# powerTestv2-0.net
KiCad netlist of a schematic drawn in EAGLE
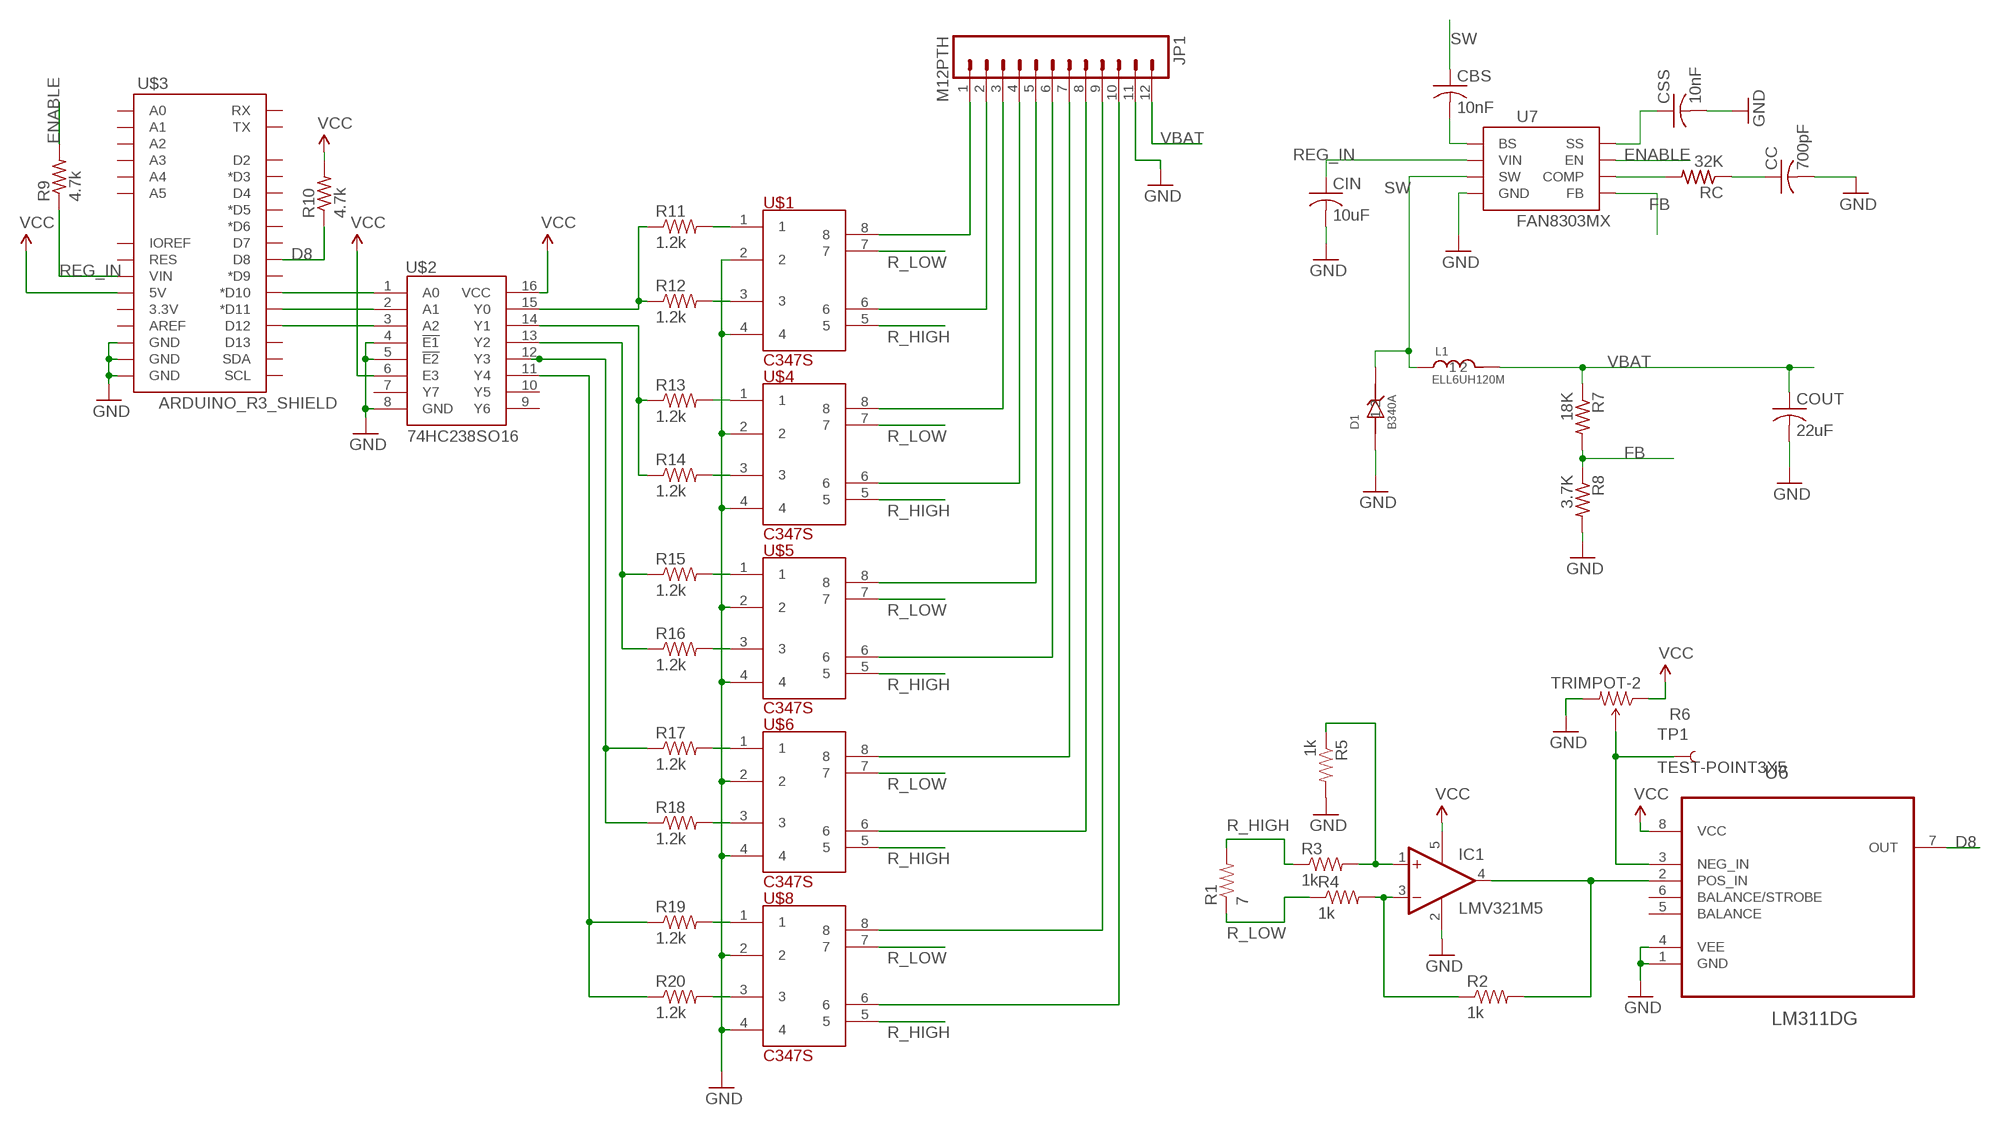
[diagram p0: schematic, sheet 1]

(export (version "E")
  (design (tool "Eeschema 10.0.6"))
  (components
    (comp (ref "CBS")
      (value "10nF")
      (footprint "eagle-import:C0603")
      (libsource (lib "eagle-import") (part "C-USC0603"))
    )
    (comp (ref "CC")
      (value "700pF")
      (footprint "eagle-import:C0603")
      (libsource (lib "eagle-import") (part "C-USC0603"))
    )
    (comp (ref "CIN")
      (value "10uF")
      (footprint "eagle-import:C0603")
      (libsource (lib "eagle-import") (part "C-USC0603"))
    )
    (comp (ref "COUT")
      (value "22uF")
      (footprint "eagle-import:C0603")
      (libsource (lib "eagle-import") (part "C-USC0603"))
    )
    (comp (ref "CSS")
      (value "10nF")
      (footprint "eagle-import:C0603")
      (libsource (lib "eagle-import") (part "C-USC0603"))
    )
    (comp (ref "D1")
      (value "B340A")
      (footprint "eagle-import:B340A")
      (libsource (lib "eagle-import") (part "B340A"))
    )
    (comp (ref "IC1")
      (value "LMV321M5")
      (footprint "eagle-import:SOT23-5")
      (libsource (lib "eagle-import") (part "LMV321?M5"))
    )
    (comp (ref "JP1")
      (value "M12PTH")
      (footprint "eagle-import:1X12")
      (libsource (lib "eagle-import") (part "M12PTH"))
    )
    (comp (ref "L1")
      (value "ELL6UH120M")
      (footprint "eagle-import:ELL6UH120M")
      (libsource (lib "eagle-import") (part "ELL6UH120M"))
    )
    (comp (ref "R1")
      (value "7")
      (footprint "eagle-import:AXIAL-0.8")
      (libsource (lib "eagle-import") (part "SparkFun-Resistors_RESISTORPTH-2W"))
    )
    (comp (ref "R2")
      (value "1k")
      (footprint "eagle-import:0603-RES")
      (libsource (lib "eagle-import") (part "RESISTOR0603-RES"))
    )
    (comp (ref "R3")
      (value "1k")
      (footprint "eagle-import:0603-RES")
      (libsource (lib "eagle-import") (part "RESISTOR0603-RES"))
    )
    (comp (ref "R4")
      (value "1k")
      (footprint "eagle-import:0603-RES")
      (libsource (lib "eagle-import") (part "RESISTOR0603-RES"))
    )
    (comp (ref "R5")
      (value "1k")
      (footprint "eagle-import:0603-RES")
      (libsource (lib "eagle-import") (part "RESISTOR0603-RES"))
    )
    (comp (ref "R6")
      (value "TRIMPOT-2")
      (footprint "eagle-import:TRIMPOT_TC33")
      (libsource (lib "eagle-import") (part "TRIMPOT-2"))
    )
    (comp (ref "R7")
      (value "18K")
      (footprint "eagle-import:R0603")
      (libsource (lib "eagle-import") (part "R-US_R0603"))
    )
    (comp (ref "R8")
      (value "3.7K")
      (footprint "eagle-import:R0603")
      (libsource (lib "eagle-import") (part "R-US_R0603"))
    )
    (comp (ref "R9")
      (value "4.7k")
      (footprint "eagle-import:R0603")
      (libsource (lib "eagle-import") (part "R-US_R0603"))
    )
    (comp (ref "R10")
      (value "4.7k")
      (footprint "eagle-import:R0603")
      (libsource (lib "eagle-import") (part "R-US_R0603"))
    )
    (comp (ref "R11")
      (value "1.2k")
      (footprint "eagle-import:0603-RES")
      (libsource (lib "eagle-import") (part "RESISTOR0603-RES"))
    )
    (comp (ref "R12")
      (value "1.2k")
      (footprint "eagle-import:0603-RES")
      (libsource (lib "eagle-import") (part "RESISTOR0603-RES"))
    )
    (comp (ref "R13")
      (value "1.2k")
      (footprint "eagle-import:0603-RES")
      (libsource (lib "eagle-import") (part "RESISTOR0603-RES"))
    )
    (comp (ref "R14")
      (value "1.2k")
      (footprint "eagle-import:0603-RES")
      (libsource (lib "eagle-import") (part "RESISTOR0603-RES"))
    )
    (comp (ref "R15")
      (value "1.2k")
      (footprint "eagle-import:0603-RES")
      (libsource (lib "eagle-import") (part "RESISTOR0603-RES"))
    )
    (comp (ref "R16")
      (value "1.2k")
      (footprint "eagle-import:0603-RES")
      (libsource (lib "eagle-import") (part "RESISTOR0603-RES"))
    )
    (comp (ref "R17")
      (value "1.2k")
      (footprint "eagle-import:0603-RES")
      (libsource (lib "eagle-import") (part "RESISTOR0603-RES"))
    )
    (comp (ref "R18")
      (value "1.2k")
      (footprint "eagle-import:0603-RES")
      (libsource (lib "eagle-import") (part "RESISTOR0603-RES"))
    )
    (comp (ref "R19")
      (value "1.2k")
      (footprint "eagle-import:0603-RES")
      (libsource (lib "eagle-import") (part "RESISTOR0603-RES"))
    )
    (comp (ref "R20")
      (value "1.2k")
      (footprint "eagle-import:0603-RES")
      (libsource (lib "eagle-import") (part "RESISTOR0603-RES"))
    )
    (comp (ref "RC")
      (value "32K")
      (footprint "eagle-import:R0603")
      (libsource (lib "eagle-import") (part "R-US_R0603"))
    )
    (comp (ref "TP1")
      (value "TEST-POINT3X5")
      (footprint "eagle-import:PAD.03X.05")
      (libsource (lib "eagle-import") (part "TEST-POINT3X5"))
    )
    (comp (ref "U$1")
      (value "C347S")
      (footprint "eagle-import:SOP8")
      (libsource (lib "eagle-import") (part "C347S"))
    )
    (comp (ref "U$2")
      (value "74HC238SO16")
      (footprint "eagle-import:SO16")
      (libsource (lib "eagle-import") (part "74HC238SO16"))
    )
    (comp (ref "U$3")
      (value "ARDUINO_R3_SHIELD")
      (footprint "eagle-import:UNO_R3_SHIELD")
      (libsource (lib "eagle-import") (part "ARDUINO_R3_SHIELD"))
    )
    (comp (ref "U$4")
      (value "C347S")
      (footprint "eagle-import:SOP8")
      (libsource (lib "eagle-import") (part "C347S"))
    )
    (comp (ref "U$5")
      (value "C347S")
      (footprint "eagle-import:SOP8")
      (libsource (lib "eagle-import") (part "C347S"))
    )
    (comp (ref "U$6")
      (value "C347S")
      (footprint "eagle-import:SOP8")
      (libsource (lib "eagle-import") (part "C347S"))
    )
    (comp (ref "U$8")
      (value "C347S")
      (footprint "eagle-import:SOP8")
      (libsource (lib "eagle-import") (part "C347S"))
    )
    (comp (ref "U6")
      (value "LM311DG")
      (footprint "eagle-import:SOIC127P600X175-8N")
      (libsource (lib "eagle-import") (part "LM311DG"))
    )
    (comp (ref "U7")
      (value "FAN8303MX")
      (footprint "eagle-import:FAN8303MX")
      (libsource (lib "eagle-import") (part "FAN8303MX"))
    )
  )
  (nets
    (net (code "1") (name "/D8") (class "Default")
      (node (ref "R10") (pin "1") (pinfunction "1_1") (pintype "passive"))
      (node (ref "U$3") (pin "D8") (pinfunction "D8_D8") (pintype "bidirectional"))
      (node (ref "U6") (pin "7") (pinfunction "OUT_7") (pintype "output"))
    )
    (net (code "2") (name "/ENABLE") (class "Default")
      (node (ref "R9") (pin "2") (pinfunction "2_2") (pintype "passive"))
      (node (ref "U7") (pin "P$7") (pinfunction "EN_P$7") (pintype "bidirectional"))
    )
    (net (code "3") (name "/FB") (class "Default")
      (node (ref "R7") (pin "2") (pinfunction "2_2") (pintype "passive"))
      (node (ref "R8") (pin "1") (pinfunction "1_1") (pintype "passive"))
      (node (ref "U7") (pin "P$5") (pinfunction "FB_P$5") (pintype "bidirectional"))
    )
    (net (code "4") (name "/REG_IN") (class "Default")
      (node (ref "CIN") (pin "1") (pinfunction "1_1") (pintype "passive"))
      (node (ref "R9") (pin "1") (pinfunction "1_1") (pintype "passive"))
      (node (ref "U$3") (pin "VIN") (pinfunction "VIN_VIN") (pintype "bidirectional"))
      (node (ref "U7") (pin "P$2") (pinfunction "VIN_P$2") (pintype "bidirectional"))
    )
    (net (code "5") (name "/R_HIGH") (class "Default")
      (node (ref "R1") (pin "P$2") (pinfunction "2_P$2") (pintype "passive"))
      (node (ref "R3") (pin "1") (pinfunction "1_1") (pintype "passive"))
      (node (ref "U$1") (pin "5") (pinfunction "5_5") (pintype "bidirectional"))
      (node (ref "U$4") (pin "5") (pinfunction "5_5") (pintype "bidirectional"))
      (node (ref "U$5") (pin "5") (pinfunction "5_5") (pintype "bidirectional"))
      (node (ref "U$6") (pin "5") (pinfunction "5_5") (pintype "bidirectional"))
      (node (ref "U$8") (pin "5") (pinfunction "5_5") (pintype "bidirectional"))
    )
    (net (code "6") (name "/R_LOW") (class "Default")
      (node (ref "R1") (pin "P$1") (pinfunction "1_P$1") (pintype "passive"))
      (node (ref "R4") (pin "1") (pinfunction "1_1") (pintype "passive"))
      (node (ref "U$1") (pin "7") (pinfunction "7_7") (pintype "bidirectional"))
      (node (ref "U$4") (pin "7") (pinfunction "7_7") (pintype "bidirectional"))
      (node (ref "U$5") (pin "7") (pinfunction "7_7") (pintype "bidirectional"))
      (node (ref "U$6") (pin "7") (pinfunction "7_7") (pintype "bidirectional"))
      (node (ref "U$8") (pin "7") (pinfunction "7_7") (pintype "bidirectional"))
    )
    (net (code "7") (name "/SW") (class "Default")
      (node (ref "CBS") (pin "1") (pinfunction "1_1") (pintype "passive"))
      (node (ref "D1") (pin "P$2") (pinfunction "2_P$2") (pintype "bidirectional"))
      (node (ref "L1") (pin "P$1") (pinfunction "1_P$1") (pintype "bidirectional"))
      (node (ref "U7") (pin "P$3") (pinfunction "SW_P$3") (pintype "bidirectional"))
    )
    (net (code "8") (name "/VBAT") (class "Default")
      (node (ref "COUT") (pin "1") (pinfunction "1_1") (pintype "passive"))
      (node (ref "JP1") (pin "12") (pinfunction "12_12") (pintype "passive"))
      (node (ref "L1") (pin "P$2") (pinfunction "2_P$2") (pintype "bidirectional"))
      (node (ref "R7") (pin "1") (pinfunction "1_1") (pintype "passive"))
    )
    (net (code "9") (name "GND") (class "Default")
      (node (ref "CC") (pin "2") (pinfunction "2_2") (pintype "passive"))
      (node (ref "CIN") (pin "2") (pinfunction "2_2") (pintype "passive"))
      (node (ref "COUT") (pin "2") (pinfunction "2_2") (pintype "passive"))
      (node (ref "CSS") (pin "2") (pinfunction "2_2") (pintype "passive"))
      (node (ref "D1") (pin "P$1") (pinfunction "1_P$1") (pintype "bidirectional"))
      (node (ref "IC1") (pin "2") (pinfunction "V-_2") (pintype "power_in"))
      (node (ref "JP1") (pin "11") (pinfunction "11_11") (pintype "passive"))
      (node (ref "R5") (pin "2") (pinfunction "2_2") (pintype "passive"))
      (node (ref "R6") (pin "3") (pinfunction "CW_3") (pintype "passive"))
      (node (ref "R8") (pin "2") (pinfunction "2_2") (pintype "passive"))
      (node (ref "U$1") (pin "2") (pinfunction "2_2") (pintype "bidirectional"))
      (node (ref "U$1") (pin "4") (pinfunction "4_4") (pintype "bidirectional"))
      (node (ref "U$2") (pin "4") (pinfunction "~{E1}_4") (pintype "input"))
      (node (ref "U$2") (pin "5") (pinfunction "~{E2}_5") (pintype "input"))
      (node (ref "U$2") (pin "8") (pinfunction "GND_8") (pintype "power_in"))
      (node (ref "U$3") (pin "GND@0") (pinfunction "GND_GND@0") (pintype "bidirectional"))
      (node (ref "U$3") (pin "GND@1") (pinfunction "GND_GND@1") (pintype "bidirectional"))
      (node (ref "U$3") (pin "GND@2") (pinfunction "GND_GND@2") (pintype "bidirectional"))
      (node (ref "U$4") (pin "2") (pinfunction "2_2") (pintype "bidirectional"))
      (node (ref "U$4") (pin "4") (pinfunction "4_4") (pintype "bidirectional"))
      (node (ref "U$5") (pin "2") (pinfunction "2_2") (pintype "bidirectional"))
      (node (ref "U$5") (pin "4") (pinfunction "4_4") (pintype "bidirectional"))
      (node (ref "U$6") (pin "2") (pinfunction "2_2") (pintype "bidirectional"))
      (node (ref "U$6") (pin "4") (pinfunction "4_4") (pintype "bidirectional"))
      (node (ref "U$8") (pin "2") (pinfunction "2_2") (pintype "bidirectional"))
      (node (ref "U$8") (pin "4") (pinfunction "4_4") (pintype "bidirectional"))
      (node (ref "U6") (pin "1") (pinfunction "GND_1") (pintype "passive"))
      (node (ref "U6") (pin "4") (pinfunction "VEE_4") (pintype "power_in"))
      (node (ref "U7") (pin "P$4") (pinfunction "GND_P$4") (pintype "bidirectional"))
    )
    (net (code "10") (name "Net-(CC-Pad1)") (class "Default")
      (node (ref "CC") (pin "1") (pinfunction "1_1") (pintype "passive"))
      (node (ref "RC") (pin "1") (pinfunction "1_1") (pintype "passive"))
    )
    (net (code "11") (name "Net-(IC1-+IN)") (class "Default")
      (node (ref "IC1") (pin "1") (pinfunction "+IN_1") (pintype "input"))
      (node (ref "R3") (pin "2") (pinfunction "2_2") (pintype "passive"))
      (node (ref "R5") (pin "1") (pinfunction "1_1") (pintype "passive"))
    )
    (net (code "12") (name "Net-(IC1--IN)") (class "Default")
      (node (ref "IC1") (pin "3") (pinfunction "-IN_3") (pintype "input"))
      (node (ref "R2") (pin "1") (pinfunction "1_1") (pintype "passive"))
      (node (ref "R4") (pin "2") (pinfunction "2_2") (pintype "passive"))
    )
    (net (code "13") (name "Net-(IC1-OUT)") (class "Default")
      (node (ref "IC1") (pin "4") (pinfunction "OUT_4") (pintype "output"))
      (node (ref "R2") (pin "2") (pinfunction "2_2") (pintype "passive"))
      (node (ref "U6") (pin "2") (pinfunction "POS_IN_2") (pintype "input"))
    )
    (net (code "14") (name "Net-(JP1-Pad1)") (class "Default")
      (node (ref "JP1") (pin "1") (pinfunction "1_1") (pintype "passive"))
      (node (ref "U$1") (pin "8") (pinfunction "8_8") (pintype "bidirectional"))
    )
    (net (code "15") (name "Net-(JP1-Pad2)") (class "Default")
      (node (ref "JP1") (pin "2") (pinfunction "2_2") (pintype "passive"))
      (node (ref "U$1") (pin "6") (pinfunction "6_6") (pintype "bidirectional"))
    )
    (net (code "16") (name "Net-(JP1-Pad3)") (class "Default")
      (node (ref "JP1") (pin "3") (pinfunction "3_3") (pintype "passive"))
      (node (ref "U$4") (pin "8") (pinfunction "8_8") (pintype "bidirectional"))
    )
    (net (code "17") (name "Net-(JP1-Pad4)") (class "Default")
      (node (ref "JP1") (pin "4") (pinfunction "4_4") (pintype "passive"))
      (node (ref "U$4") (pin "6") (pinfunction "6_6") (pintype "bidirectional"))
    )
    (net (code "18") (name "Net-(JP1-Pad5)") (class "Default")
      (node (ref "JP1") (pin "5") (pinfunction "5_5") (pintype "passive"))
      (node (ref "U$5") (pin "8") (pinfunction "8_8") (pintype "bidirectional"))
    )
    (net (code "19") (name "Net-(JP1-Pad6)") (class "Default")
      (node (ref "JP1") (pin "6") (pinfunction "6_6") (pintype "passive"))
      (node (ref "U$5") (pin "6") (pinfunction "6_6") (pintype "bidirectional"))
    )
    (net (code "20") (name "Net-(JP1-Pad7)") (class "Default")
      (node (ref "JP1") (pin "7") (pinfunction "7_7") (pintype "passive"))
      (node (ref "U$6") (pin "8") (pinfunction "8_8") (pintype "bidirectional"))
    )
    (net (code "21") (name "Net-(JP1-Pad8)") (class "Default")
      (node (ref "JP1") (pin "8") (pinfunction "8_8") (pintype "passive"))
      (node (ref "U$6") (pin "6") (pinfunction "6_6") (pintype "bidirectional"))
    )
    (net (code "22") (name "Net-(JP1-Pad9)") (class "Default")
      (node (ref "JP1") (pin "9") (pinfunction "9_9") (pintype "passive"))
      (node (ref "U$8") (pin "8") (pinfunction "8_8") (pintype "bidirectional"))
    )
    (net (code "23") (name "Net-(JP1-Pad10)") (class "Default")
      (node (ref "JP1") (pin "10") (pinfunction "10_10") (pintype "passive"))
      (node (ref "U$8") (pin "6") (pinfunction "6_6") (pintype "bidirectional"))
    )
    (net (code "24") (name "Net-(R6-WIPER)") (class "Default")
      (node (ref "R6") (pin "2") (pinfunction "WIPER_2") (pintype "passive"))
      (node (ref "TP1") (pin "P$1") (pinfunction "1_P$1") (pintype "bidirectional"))
      (node (ref "U6") (pin "3") (pinfunction "NEG_IN_3") (pintype "input"))
    )
    (net (code "25") (name "Net-(R11-Pad2)") (class "Default")
      (node (ref "R11") (pin "2") (pinfunction "2_2") (pintype "passive"))
      (node (ref "U$1") (pin "1") (pinfunction "1_1") (pintype "bidirectional"))
    )
    (net (code "26") (name "Net-(R12-Pad2)") (class "Default")
      (node (ref "R12") (pin "2") (pinfunction "2_2") (pintype "passive"))
      (node (ref "U$1") (pin "3") (pinfunction "3_3") (pintype "bidirectional"))
    )
    (net (code "27") (name "Net-(R13-Pad2)") (class "Default")
      (node (ref "R13") (pin "2") (pinfunction "2_2") (pintype "passive"))
      (node (ref "U$4") (pin "1") (pinfunction "1_1") (pintype "bidirectional"))
    )
    (net (code "28") (name "Net-(R14-Pad2)") (class "Default")
      (node (ref "R14") (pin "2") (pinfunction "2_2") (pintype "passive"))
      (node (ref "U$4") (pin "3") (pinfunction "3_3") (pintype "bidirectional"))
    )
    (net (code "29") (name "Net-(R15-Pad2)") (class "Default")
      (node (ref "R15") (pin "2") (pinfunction "2_2") (pintype "passive"))
      (node (ref "U$5") (pin "1") (pinfunction "1_1") (pintype "bidirectional"))
    )
    (net (code "30") (name "Net-(R16-Pad2)") (class "Default")
      (node (ref "R16") (pin "2") (pinfunction "2_2") (pintype "passive"))
      (node (ref "U$5") (pin "3") (pinfunction "3_3") (pintype "bidirectional"))
    )
    (net (code "31") (name "Net-(R17-Pad2)") (class "Default")
      (node (ref "R17") (pin "2") (pinfunction "2_2") (pintype "passive"))
      (node (ref "U$6") (pin "1") (pinfunction "1_1") (pintype "bidirectional"))
    )
    (net (code "32") (name "Net-(R18-Pad2)") (class "Default")
      (node (ref "R18") (pin "2") (pinfunction "2_2") (pintype "passive"))
      (node (ref "U$6") (pin "3") (pinfunction "3_3") (pintype "bidirectional"))
    )
    (net (code "33") (name "Net-(R19-Pad2)") (class "Default")
      (node (ref "R19") (pin "2") (pinfunction "2_2") (pintype "passive"))
      (node (ref "U$8") (pin "1") (pinfunction "1_1") (pintype "bidirectional"))
    )
    (net (code "34") (name "Net-(R20-Pad2)") (class "Default")
      (node (ref "R20") (pin "2") (pinfunction "2_2") (pintype "passive"))
      (node (ref "U$8") (pin "3") (pinfunction "3_3") (pintype "bidirectional"))
    )
    (net (code "35") (name "Net-(U$2-A0)") (class "Default")
      (node (ref "U$2") (pin "1") (pinfunction "A0_1") (pintype "input"))
      (node (ref "U$3") (pin "D10") (pinfunction "*D10_D10") (pintype "bidirectional"))
    )
    (net (code "36") (name "Net-(U$2-A1)") (class "Default")
      (node (ref "U$2") (pin "2") (pinfunction "A1_2") (pintype "input"))
      (node (ref "U$3") (pin "D11") (pinfunction "*D11_D11") (pintype "bidirectional"))
    )
    (net (code "37") (name "Net-(U$2-A2)") (class "Default")
      (node (ref "U$2") (pin "3") (pinfunction "A2_3") (pintype "input"))
      (node (ref "U$3") (pin "D12") (pinfunction "D12_D12") (pintype "bidirectional"))
    )
    (net (code "38") (name "Net-(U$2-Y0)") (class "Default")
      (node (ref "R11") (pin "1") (pinfunction "1_1") (pintype "passive"))
      (node (ref "R12") (pin "1") (pinfunction "1_1") (pintype "passive"))
      (node (ref "U$2") (pin "15") (pinfunction "Y0_15") (pintype "output"))
    )
    (net (code "39") (name "Net-(U$2-Y1)") (class "Default")
      (node (ref "R13") (pin "1") (pinfunction "1_1") (pintype "passive"))
      (node (ref "R14") (pin "1") (pinfunction "1_1") (pintype "passive"))
      (node (ref "U$2") (pin "14") (pinfunction "Y1_14") (pintype "output"))
    )
    (net (code "40") (name "Net-(U$2-Y2)") (class "Default")
      (node (ref "R15") (pin "1") (pinfunction "1_1") (pintype "passive"))
      (node (ref "R16") (pin "1") (pinfunction "1_1") (pintype "passive"))
      (node (ref "U$2") (pin "13") (pinfunction "Y2_13") (pintype "output"))
    )
    (net (code "41") (name "Net-(U$2-Y3)") (class "Default")
      (node (ref "R17") (pin "1") (pinfunction "1_1") (pintype "passive"))
      (node (ref "R18") (pin "1") (pinfunction "1_1") (pintype "passive"))
      (node (ref "U$2") (pin "12") (pinfunction "Y3_12") (pintype "output"))
    )
    (net (code "42") (name "Net-(U$2-Y4)") (class "Default")
      (node (ref "R19") (pin "1") (pinfunction "1_1") (pintype "passive"))
      (node (ref "R20") (pin "1") (pinfunction "1_1") (pintype "passive"))
      (node (ref "U$2") (pin "11") (pinfunction "Y4_11") (pintype "output"))
    )
    (net (code "43") (name "Net-(U7-BS)") (class "Default")
      (node (ref "CBS") (pin "2") (pinfunction "2_2") (pintype "passive"))
      (node (ref "U7") (pin "P$1") (pinfunction "BS_P$1") (pintype "bidirectional"))
    )
    (net (code "44") (name "Net-(U7-COMP)") (class "Default")
      (node (ref "RC") (pin "2") (pinfunction "2_2") (pintype "passive"))
      (node (ref "U7") (pin "P$6") (pinfunction "COMP_P$6") (pintype "bidirectional"))
    )
    (net (code "45") (name "Net-(U7-SS)") (class "Default")
      (node (ref "CSS") (pin "1") (pinfunction "1_1") (pintype "passive"))
      (node (ref "U7") (pin "P$8") (pinfunction "SS_P$8") (pintype "bidirectional"))
    )
    (net (code "46") (name "VCC") (class "Default")
      (node (ref "IC1") (pin "5") (pinfunction "V+_5") (pintype "power_in"))
      (node (ref "R10") (pin "2") (pinfunction "2_2") (pintype "passive"))
      (node (ref "R6") (pin "1") (pinfunction "CCW_1") (pintype "passive"))
      (node (ref "U$2") (pin "16") (pinfunction "VCC_16") (pintype "power_in"))
      (node (ref "U$2") (pin "6") (pinfunction "E3_6") (pintype "input"))
      (node (ref "U$3") (pin "5V") (pinfunction "5V_5V") (pintype "bidirectional"))
      (node (ref "U6") (pin "8") (pinfunction "VCC_8") (pintype "power_in"))
    )
    (net (code "47") (name "unconnected-(U$2-Y5-Pad10)") (class "Default")
      (node (ref "U$2") (pin "10") (pinfunction "Y5_10") (pintype "output"))
    )
    (net (code "48") (name "unconnected-(U$2-Y6-Pad9)") (class "Default")
      (node (ref "U$2") (pin "9") (pinfunction "Y6_9") (pintype "output"))
    )
    (net (code "49") (name "unconnected-(U$2-Y7-Pad7)") (class "Default")
      (node (ref "U$2") (pin "7") (pinfunction "Y7_7") (pintype "output"))
    )
    (net (code "50") (name "unconnected-(U$3-*D3-PadD3)") (class "Default")
      (node (ref "U$3") (pin "D3") (pinfunction "*D3_D3") (pintype "bidirectional"))
    )
    (net (code "51") (name "unconnected-(U$3-*D5-PadD5)") (class "Default")
      (node (ref "U$3") (pin "D5") (pinfunction "*D5_D5") (pintype "bidirectional"))
    )
    (net (code "52") (name "unconnected-(U$3-*D6-PadD6)") (class "Default")
      (node (ref "U$3") (pin "D6") (pinfunction "*D6_D6") (pintype "bidirectional"))
    )
    (net (code "53") (name "unconnected-(U$3-*D9-PadD9)") (class "Default")
      (node (ref "U$3") (pin "D9") (pinfunction "*D9_D9") (pintype "bidirectional"))
    )
    (net (code "54") (name "unconnected-(U$3-Pad3.3V)") (class "Default")
      (node (ref "U$3") (pin "3.3V") (pinfunction "3.3V_3.3V") (pintype "bidirectional"))
    )
    (net (code "55") (name "unconnected-(U$3-PadA0)") (class "Default")
      (node (ref "U$3") (pin "A0") (pinfunction "A0_A0") (pintype "bidirectional"))
    )
    (net (code "56") (name "unconnected-(U$3-PadA1)") (class "Default")
      (node (ref "U$3") (pin "A1") (pinfunction "A1_A1") (pintype "bidirectional"))
    )
    (net (code "57") (name "unconnected-(U$3-PadA2)") (class "Default")
      (node (ref "U$3") (pin "A2") (pinfunction "A2_A2") (pintype "bidirectional"))
    )
    (net (code "58") (name "unconnected-(U$3-PadA3)") (class "Default")
      (node (ref "U$3") (pin "A3") (pinfunction "A3_A3") (pintype "bidirectional"))
    )
    (net (code "59") (name "unconnected-(U$3-PadA4)") (class "Default")
      (node (ref "U$3") (pin "A4") (pinfunction "A4_A4") (pintype "bidirectional"))
    )
    (net (code "60") (name "unconnected-(U$3-PadA5)") (class "Default")
      (node (ref "U$3") (pin "A5") (pinfunction "A5_A5") (pintype "bidirectional"))
    )
    (net (code "61") (name "unconnected-(U$3-PadAREF)") (class "Default")
      (node (ref "U$3") (pin "AREF") (pinfunction "AREF_AREF") (pintype "bidirectional"))
    )
    (net (code "62") (name "unconnected-(U$3-PadD2)") (class "Default")
      (node (ref "U$3") (pin "D2") (pinfunction "D2_D2") (pintype "bidirectional"))
    )
    (net (code "63") (name "unconnected-(U$3-PadD4)") (class "Default")
      (node (ref "U$3") (pin "D4") (pinfunction "D4_D4") (pintype "bidirectional"))
    )
    (net (code "64") (name "unconnected-(U$3-PadD7)") (class "Default")
      (node (ref "U$3") (pin "D7") (pinfunction "D7_D7") (pintype "bidirectional"))
    )
    (net (code "65") (name "unconnected-(U$3-PadD13)") (class "Default")
      (node (ref "U$3") (pin "D13") (pinfunction "D13_D13") (pintype "bidirectional"))
    )
    (net (code "66") (name "unconnected-(U$3-PadIOREF)") (class "Default")
      (node (ref "U$3") (pin "IOREF") (pinfunction "IOREF_IOREF") (pintype "bidirectional"))
    )
    (net (code "67") (name "unconnected-(U$3-PadRES)") (class "Default")
      (node (ref "U$3") (pin "RES") (pinfunction "RES_RES") (pintype "bidirectional"))
    )
    (net (code "68") (name "unconnected-(U$3-PadRX)") (class "Default")
      (node (ref "U$3") (pin "RX") (pinfunction "RX_RX") (pintype "bidirectional"))
    )
    (net (code "69") (name "unconnected-(U$3-PadSCL)") (class "Default")
      (node (ref "U$3") (pin "SCL") (pinfunction "SCL_SCL") (pintype "bidirectional"))
    )
    (net (code "70") (name "unconnected-(U$3-PadSDA)") (class "Default")
      (node (ref "U$3") (pin "SDA") (pinfunction "SDA_SDA") (pintype "bidirectional"))
    )
    (net (code "71") (name "unconnected-(U$3-PadTX)") (class "Default")
      (node (ref "U$3") (pin "TX") (pinfunction "TX_TX") (pintype "bidirectional"))
    )
    (net (code "72") (name "unconnected-(U6-BALANCE-Pad5)") (class "Default")
      (node (ref "U6") (pin "5") (pinfunction "BALANCE_5") (pintype "input"))
    )
    (net (code "73") (name "unconnected-(U6-BALANCE{slash}STROBE-Pad6)") (class "Default")
      (node (ref "U6") (pin "6") (pinfunction "BALANCE/STROBE_6") (pintype "input"))
    )
  )
)
